# Current_regulation.net
KiCad netlist of a schematic drawn in Altium Designer
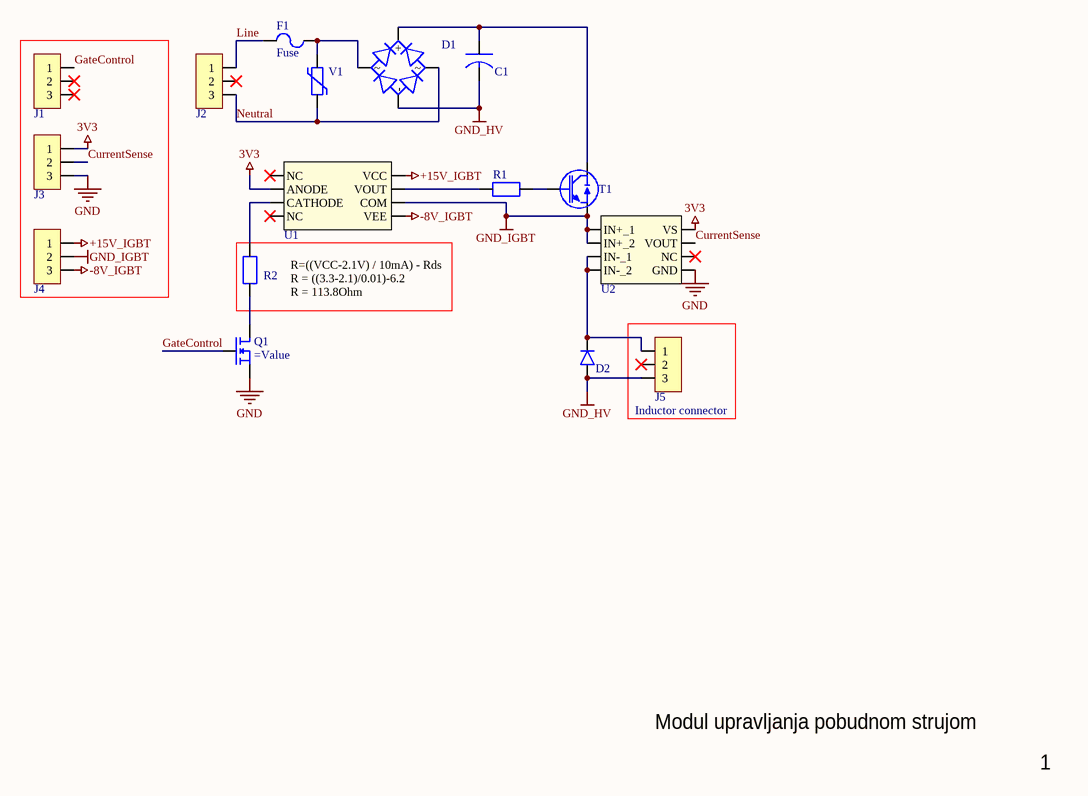
[diagram p0: Current_regulation.SchDoc]

(export (version "E")
  (design (tool "Eeschema 10.0.6"))
  (components
    (comp (ref "C1")
      (value "Capacitor-P")
      (footprint "C-P-400V")
      (libsource (lib "Symbols") (part "Capacitor-P"))
    )
    (comp (ref "D1")
      (value "KBJ2010_T0_00601")
      (footprint "SIP480W100P750L2530H1340Q4")
      (libsource (lib "Database_Libs") (part "Full_Bridge_Rectifier"))
    )
    (comp (ref "D2")
      (value "Diode")
      (footprint "Footprints:Diode-6A")
      (libsource (lib "Symbols") (part "Diode"))
    )
    (comp (ref "F1")
      (value "Fuse")
      (footprint "Footprints:FuseHolder")
      (fields (field (name "PART NUMBER") "F_30A"))
      (libsource (lib "Database_Libs") (part "Fuse"))
    )
    (comp (ref "J1")
      (value "Molex Micro-Latch")
      (footprint "Footprints:ScrewTerminal")
      (fields
        (field (name "PART NUMBER") "Molex Micro-Latch 1x3")
        (field (name "MANUFACTURER PART NUMBER") "53254-0370")
      )
      (libsource (lib "Database_Libs") (part "Header_1x3"))
    )
    (comp (ref "J2")
      (value "Molex Micro-Latch")
      (footprint "Footprints:ScrewTerminal")
      (fields
        (field (name "PART NUMBER") "Molex Micro-Latch 1x3")
        (field (name "MANUFACTURER PART NUMBER") "53254-0370")
      )
      (libsource (lib "Database_Libs") (part "Header_1x3"))
    )
    (comp (ref "J3")
      (value "Molex Micro-Latch")
      (footprint "Footprints:ScrewTerminal")
      (fields
        (field (name "PART NUMBER") "Molex Micro-Latch 1x3")
        (field (name "MANUFACTURER PART NUMBER") "53254-0370")
      )
      (libsource (lib "Database_Libs") (part "Header_1x3"))
    )
    (comp (ref "J4")
      (value "Molex Micro-Latch")
      (footprint "Footprints:ScrewTerminal")
      (fields
        (field (name "PART NUMBER") "Molex Micro-Latch 1x3")
        (field (name "MANUFACTURER PART NUMBER") "53254-0370")
      )
      (libsource (lib "Database_Libs") (part "Header_1x3"))
    )
    (comp (ref "J5")
      (value "Molex Micro-Latch")
      (footprint "Footprints:ScrewTerminal")
      (fields
        (field (name "PART NUMBER") "Molex Micro-Latch 1x3")
        (field (name "MANUFACTURER PART NUMBER") "53254-0370")
      )
      (libsource (lib "") (part "Header_1x3_1"))
    )
    (comp (ref "Q1") (value "~") (footprint "MOSFET") (libsource (lib "Symbols") (part "MOSFET")))
    (comp (ref "R1")
      (value "1k")
      (footprint "Footprints:R-2W")
      (libsource (lib "Resistor") (part "Resistor"))
    )
    (comp (ref "R2") (value "120Ohm") (footprint "Footprints:R-2W") (libsource (lib "") (part "Resistor_1")))
    (comp (ref "T1")
      (value "IKA08N65ET6XKSA1")
      (footprint "TO254P1065X485X2200-3")
      (libsource (lib "Database_Libs") (part "IGBT_with_diode"))
    )
    (comp (ref "U1")
      (value "UCC23514EDWVR")
      (footprint "SOIC8P127_585X1150X280L75X41N")
      (libsource (lib "Database_Libs") (part "UCC23514EDWVR"))
    )
    (comp (ref "U2")
      (value "TMCS1108A3BQDT")
      (footprint "SOIC8P127_490X599X200L104X41N")
      (libsource (lib "Database_Libs") (part "TMCS1108A3BQDT"))
    )
    (comp (ref "V1")
      (value "Varistor")
      (footprint "VARRBO750W80L1350T640H1650")
      (fields (field (name "PART NUMBER") "B72314S2351K101"))
      (libsource (lib "Database_Libs") (part "Varistor"))
    )
  )
  (nets
    (net (code "1") (name "+15V_IGBT") (class "Default")
      (node (ref "J4") (pin "1") (pinfunction "1_1") (pintype "passive"))
      (node (ref "U1") (pin "8") (pinfunction "VCC_8") (pintype "power_in"))
    )
    (net (code "2") (name "-8V_IGBT") (class "Default")
      (node (ref "J4") (pin "3") (pinfunction "3_3") (pintype "passive"))
      (node (ref "U1") (pin "5") (pinfunction "VEE_5") (pintype "power_in"))
    )
    (net (code "3") (name "/CurrentSense") (class "Default")
      (node (ref "J3") (pin "2") (pinfunction "2_2") (pintype "passive"))
      (node (ref "U2") (pin "7") (pinfunction "VOUT_7") (pintype "passive"))
    )
    (net (code "4") (name "/GateControl") (class "Default")
      (node (ref "J1") (pin "1") (pinfunction "1_1") (pintype "passive"))
      (node (ref "Q1") (pin "1") (pinfunction "1_1") (pintype "passive"))
    )
    (net (code "5") (name "/Line") (class "Default")
      (node (ref "F1") (pin "1") (pinfunction "1_1") (pintype "passive"))
      (node (ref "J2") (pin "1") (pinfunction "1_1") (pintype "passive"))
    )
    (net (code "6") (name "/Neutral") (class "Default")
      (node (ref "D1") (pin "4") (pinfunction "~_4") (pintype "passive"))
      (node (ref "J2") (pin "3") (pinfunction "3_3") (pintype "passive"))
      (node (ref "V1") (pin "1") (pinfunction "1_1") (pintype "passive"))
    )
    (net (code "7") (name "3V3") (class "Default")
      (node (ref "J3") (pin "1") (pinfunction "1_1") (pintype "passive"))
      (node (ref "U1") (pin "2") (pinfunction "ANODE_2") (pintype "passive"))
      (node (ref "U2") (pin "8") (pinfunction "VS_8") (pintype "power_in"))
    )
    (net (code "8") (name "GND") (class "Default")
      (node (ref "J3") (pin "3") (pinfunction "3_3") (pintype "passive"))
      (node (ref "Q1") (pin "3") (pinfunction "3_3") (pintype "passive"))
      (node (ref "U2") (pin "5") (pinfunction "GND_5") (pintype "power_in"))
    )
    (net (code "9") (name "GND_HV") (class "Default")
      (node (ref "C1") (pin "1") (pinfunction "1_1") (pintype "passive"))
      (node (ref "D1") (pin "2") (pinfunction "-_2") (pintype "passive"))
      (node (ref "D2") (pin "A") (pinfunction "A_A") (pintype "passive"))
      (node (ref "J5") (pin "3") (pinfunction "3_3") (pintype "passive"))
    )
    (net (code "10") (name "GND_IGBT") (class "Default")
      (node (ref "J4") (pin "2") (pinfunction "2_2") (pintype "passive"))
      (node (ref "T1") (pin "3") (pinfunction "E_3") (pintype "passive"))
      (node (ref "U1") (pin "6") (pinfunction "COM_6") (pintype "power_in"))
      (node (ref "U2") (pin "1") (pinfunction "IN+_1_1") (pintype "passive"))
      (node (ref "U2") (pin "2") (pinfunction "IN+_2_2") (pintype "passive"))
    )
    (net (code "11") (name "Net-(D1-+)") (class "Default")
      (node (ref "C1") (pin "2") (pinfunction "2_2") (pintype "passive"))
      (node (ref "D1") (pin "1") (pinfunction "+_1") (pintype "passive"))
      (node (ref "T1") (pin "2") (pinfunction "C_2") (pintype "passive"))
    )
    (net (code "12") (name "Net-(D1-~-Pad3)") (class "Default")
      (node (ref "D1") (pin "3") (pinfunction "~_3") (pintype "passive"))
      (node (ref "F1") (pin "2") (pinfunction "2_2") (pintype "passive"))
      (node (ref "V1") (pin "2") (pinfunction "2_2") (pintype "passive"))
    )
    (net (code "13") (name "Net-(Q1-Pad2)") (class "Default")
      (node (ref "Q1") (pin "2") (pinfunction "2_2") (pintype "passive"))
      (node (ref "R2") (pin "2") (pinfunction "2_2") (pintype "passive"))
    )
    (net (code "14") (name "Net-(T1-G)") (class "Default")
      (node (ref "R1") (pin "1") (pinfunction "1_1") (pintype "passive"))
      (node (ref "T1") (pin "1") (pinfunction "G_1") (pintype "passive"))
    )
    (net (code "15") (name "Net-(U1-CATHODE)") (class "Default")
      (node (ref "R2") (pin "1") (pinfunction "1_1") (pintype "passive"))
      (node (ref "U1") (pin "3") (pinfunction "CATHODE_3") (pintype "passive"))
    )
    (net (code "16") (name "Net-(U1-VOUT)") (class "Default")
      (node (ref "R1") (pin "2") (pinfunction "2_2") (pintype "passive"))
      (node (ref "U1") (pin "7") (pinfunction "VOUT_7") (pintype "passive"))
    )
    (net (code "17") (name "Net-(U2-IN-_1)") (class "Default")
      (node (ref "D2") (pin "C") (pinfunction "C_C") (pintype "passive"))
      (node (ref "J5") (pin "1") (pinfunction "1_1") (pintype "passive"))
      (node (ref "U2") (pin "3") (pinfunction "IN-_1_3") (pintype "passive"))
      (node (ref "U2") (pin "4") (pinfunction "IN-_2_4") (pintype "passive"))
    )
    (net (code "18") (name "unconnected-(J1-Pad2)") (class "Default")
      (node (ref "J1") (pin "2") (pinfunction "2_2") (pintype "passive+no_connect"))
    )
    (net (code "19") (name "unconnected-(J1-Pad3)") (class "Default")
      (node (ref "J1") (pin "3") (pinfunction "3_3") (pintype "passive+no_connect"))
    )
    (net (code "20") (name "unconnected-(J2-Pad2)") (class "Default")
      (node (ref "J2") (pin "2") (pinfunction "2_2") (pintype "passive+no_connect"))
    )
    (net (code "21") (name "unconnected-(J5-Pad2)") (class "Default")
      (node (ref "J5") (pin "2") (pinfunction "2_2") (pintype "passive+no_connect"))
    )
    (net (code "22") (name "unconnected-(U1-NC-Pad1)") (class "Default")
      (node (ref "U1") (pin "1") (pinfunction "NC_1") (pintype "passive+no_connect"))
    )
    (net (code "23") (name "unconnected-(U1-NC-Pad4)") (class "Default")
      (node (ref "U1") (pin "4") (pinfunction "NC_4") (pintype "passive+no_connect"))
    )
    (net (code "24") (name "unconnected-(U2-NC-Pad6)") (class "Default")
      (node (ref "U2") (pin "6") (pinfunction "NC_6") (pintype "passive+no_connect"))
    )
  )
)
